# axiom_beta_plugin_module_3xPMOD_v1_1_1d7.net
KiCad netlist of a schematic drawn in EAGLE
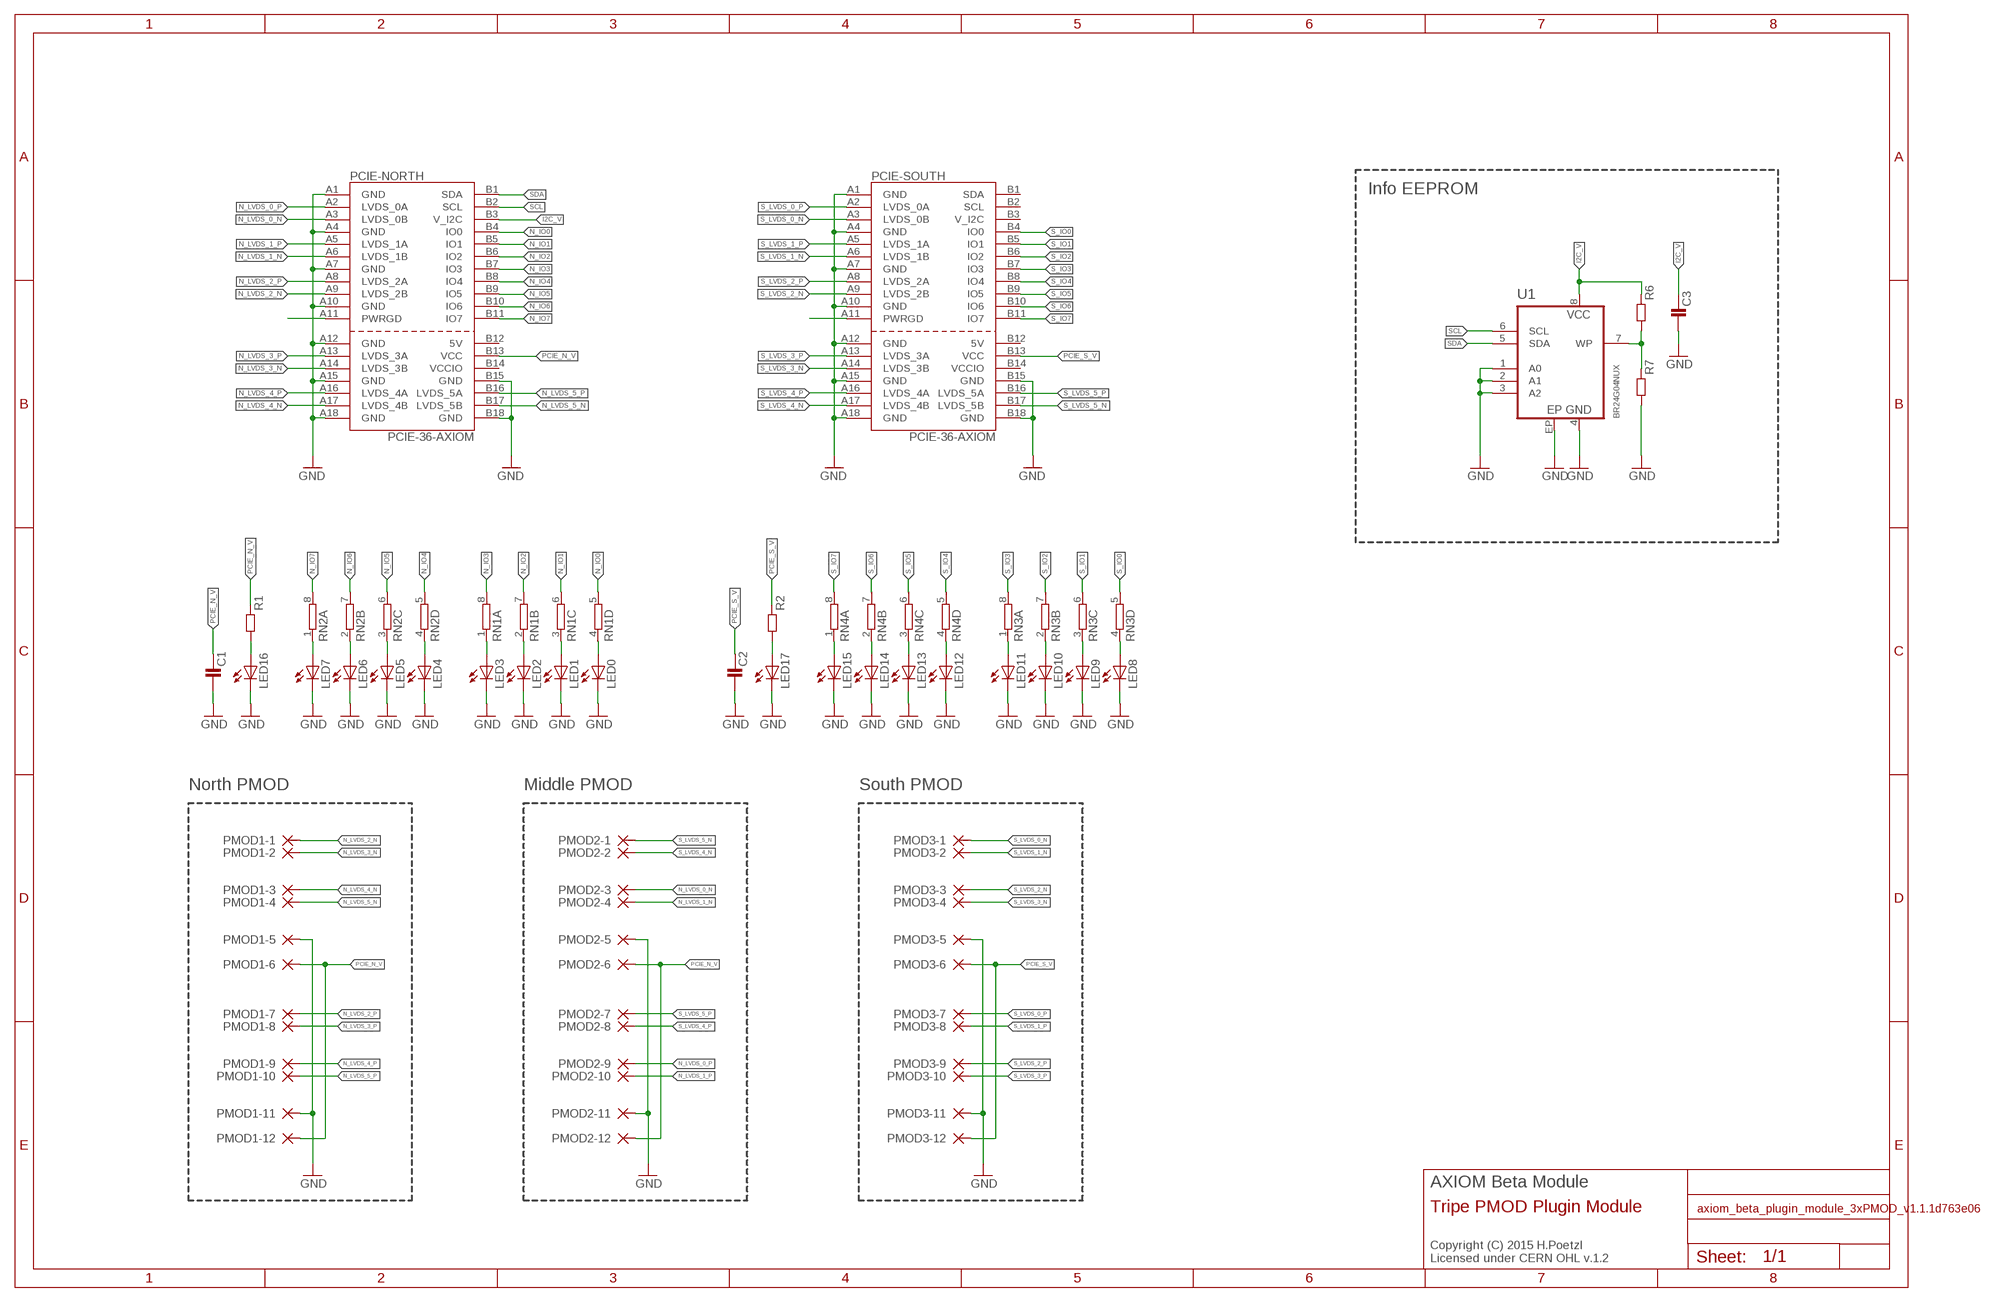
[diagram p0: schematic, sheet 1]

(export (version "E")
  (design (tool "Eeschema 10.0.6"))
  (components
    (comp (ref "C1")
      (value "C1206-A")
      (footprint "eagle-import:1206-A")
      (libsource (lib "eagle-import") (part "C1206-A"))
    )
    (comp (ref "C2")
      (value "C1206-A")
      (footprint "eagle-import:1206-A")
      (libsource (lib "eagle-import") (part "C1206-A"))
    )
    (comp (ref "C3")
      (value "C0402-B")
      (footprint "eagle-import:0402-B")
      (libsource (lib "eagle-import") (part "C0402-B"))
    )
    (comp (ref "LED0")
      (value "LEDCHIPLED_0603")
      (footprint "eagle-import:CHIPLED_0603")
      (libsource (lib "eagle-import") (part "LEDCHIPLED_0603"))
    )
    (comp (ref "LED1")
      (value "LEDCHIPLED_0603")
      (footprint "eagle-import:CHIPLED_0603")
      (libsource (lib "eagle-import") (part "LEDCHIPLED_0603"))
    )
    (comp (ref "LED2")
      (value "LEDCHIPLED_0603")
      (footprint "eagle-import:CHIPLED_0603")
      (libsource (lib "eagle-import") (part "LEDCHIPLED_0603"))
    )
    (comp (ref "LED3")
      (value "LEDCHIPLED_0603")
      (footprint "eagle-import:CHIPLED_0603")
      (libsource (lib "eagle-import") (part "LEDCHIPLED_0603"))
    )
    (comp (ref "LED4")
      (value "LEDCHIPLED_0603")
      (footprint "eagle-import:CHIPLED_0603")
      (libsource (lib "eagle-import") (part "LEDCHIPLED_0603"))
    )
    (comp (ref "LED5")
      (value "LEDCHIPLED_0603")
      (footprint "eagle-import:CHIPLED_0603")
      (libsource (lib "eagle-import") (part "LEDCHIPLED_0603"))
    )
    (comp (ref "LED6")
      (value "LEDCHIPLED_0603")
      (footprint "eagle-import:CHIPLED_0603")
      (libsource (lib "eagle-import") (part "LEDCHIPLED_0603"))
    )
    (comp (ref "LED7")
      (value "LEDCHIPLED_0603")
      (footprint "eagle-import:CHIPLED_0603")
      (libsource (lib "eagle-import") (part "LEDCHIPLED_0603"))
    )
    (comp (ref "LED8")
      (value "LEDCHIPLED_0603")
      (footprint "eagle-import:CHIPLED_0603")
      (libsource (lib "eagle-import") (part "LEDCHIPLED_0603"))
    )
    (comp (ref "LED9")
      (value "LEDCHIPLED_0603")
      (footprint "eagle-import:CHIPLED_0603")
      (libsource (lib "eagle-import") (part "LEDCHIPLED_0603"))
    )
    (comp (ref "LED10")
      (value "LEDCHIPLED_0603")
      (footprint "eagle-import:CHIPLED_0603")
      (libsource (lib "eagle-import") (part "LEDCHIPLED_0603"))
    )
    (comp (ref "LED11")
      (value "LEDCHIPLED_0603")
      (footprint "eagle-import:CHIPLED_0603")
      (libsource (lib "eagle-import") (part "LEDCHIPLED_0603"))
    )
    (comp (ref "LED12")
      (value "LEDCHIPLED_0603")
      (footprint "eagle-import:CHIPLED_0603")
      (libsource (lib "eagle-import") (part "LEDCHIPLED_0603"))
    )
    (comp (ref "LED13")
      (value "LEDCHIPLED_0603")
      (footprint "eagle-import:CHIPLED_0603")
      (libsource (lib "eagle-import") (part "LEDCHIPLED_0603"))
    )
    (comp (ref "LED14")
      (value "LEDCHIPLED_0603")
      (footprint "eagle-import:CHIPLED_0603")
      (libsource (lib "eagle-import") (part "LEDCHIPLED_0603"))
    )
    (comp (ref "LED15")
      (value "LEDCHIPLED_0603")
      (footprint "eagle-import:CHIPLED_0603")
      (libsource (lib "eagle-import") (part "LEDCHIPLED_0603"))
    )
    (comp (ref "LED16")
      (value "LEDCHIPLED_0603")
      (footprint "eagle-import:CHIPLED_0603")
      (libsource (lib "eagle-import") (part "LEDCHIPLED_0603"))
    )
    (comp (ref "LED17")
      (value "LEDCHIPLED_0603")
      (footprint "eagle-import:CHIPLED_0603")
      (libsource (lib "eagle-import") (part "LEDCHIPLED_0603"))
    )
    (comp (ref "PCIE-NORTH")
      (value "PCIE-36-AXIOM")
      (footprint "eagle-import:PCIE-36-AXIOM")
      (libsource (lib "eagle-import") (part "PCIE-36-AXIOM"))
    )
    (comp (ref "PCIE-SOUTH")
      (value "PCIE-36-AXIOM")
      (footprint "eagle-import:PCIE-36-AXIOM")
      (libsource (lib "eagle-import") (part "PCIE-36-AXIOM"))
    )
    (comp (ref "PMOD1-1")
      (value "SMD-PAD1.6X3.8MM-U")
      (footprint "eagle-import:1.6X3.8U-MM")
      (libsource (lib "eagle-import") (part "SMD-PAD1.6X3.8MM-U"))
    )
    (comp (ref "PMOD1-2")
      (value "SMD-PAD1.6X3.8MM-U")
      (footprint "eagle-import:1.6X3.8U-MM")
      (libsource (lib "eagle-import") (part "SMD-PAD1.6X3.8MM-U"))
    )
    (comp (ref "PMOD1-3")
      (value "SMD-PAD1.6X3.8MM-U")
      (footprint "eagle-import:1.6X3.8U-MM")
      (libsource (lib "eagle-import") (part "SMD-PAD1.6X3.8MM-U"))
    )
    (comp (ref "PMOD1-4")
      (value "SMD-PAD1.6X3.8MM-U")
      (footprint "eagle-import:1.6X3.8U-MM")
      (libsource (lib "eagle-import") (part "SMD-PAD1.6X3.8MM-U"))
    )
    (comp (ref "PMOD1-5")
      (value "SMD-PAD1.6X3.8MM-U")
      (footprint "eagle-import:1.6X3.8U-MM")
      (libsource (lib "eagle-import") (part "SMD-PAD1.6X3.8MM-U"))
    )
    (comp (ref "PMOD1-6")
      (value "SMD-PAD1.6X3.8MM-U")
      (footprint "eagle-import:1.6X3.8U-MM")
      (libsource (lib "eagle-import") (part "SMD-PAD1.6X3.8MM-U"))
    )
    (comp (ref "PMOD1-7")
      (value "SMD-PAD1.6X3.8MM-U")
      (footprint "eagle-import:1.6X3.8U-MM")
      (libsource (lib "eagle-import") (part "SMD-PAD1.6X3.8MM-U"))
    )
    (comp (ref "PMOD1-8")
      (value "SMD-PAD1.6X3.8MM-U")
      (footprint "eagle-import:1.6X3.8U-MM")
      (libsource (lib "eagle-import") (part "SMD-PAD1.6X3.8MM-U"))
    )
    (comp (ref "PMOD1-9")
      (value "SMD-PAD1.6X3.8MM-U")
      (footprint "eagle-import:1.6X3.8U-MM")
      (libsource (lib "eagle-import") (part "SMD-PAD1.6X3.8MM-U"))
    )
    (comp (ref "PMOD1-10")
      (value "SMD-PAD1.6X3.8MM-U")
      (footprint "eagle-import:1.6X3.8U-MM")
      (libsource (lib "eagle-import") (part "SMD-PAD1.6X3.8MM-U"))
    )
    (comp (ref "PMOD1-11")
      (value "SMD-PAD1.6X3.8MM-U")
      (footprint "eagle-import:1.6X3.8U-MM")
      (libsource (lib "eagle-import") (part "SMD-PAD1.6X3.8MM-U"))
    )
    (comp (ref "PMOD1-12")
      (value "SMD-PAD1.6X3.8MM-U")
      (footprint "eagle-import:1.6X3.8U-MM")
      (libsource (lib "eagle-import") (part "SMD-PAD1.6X3.8MM-U"))
    )
    (comp (ref "PMOD2-1")
      (value "SMD-PAD1.6X3.8MM-U")
      (footprint "eagle-import:1.6X3.8U-MM")
      (libsource (lib "eagle-import") (part "SMD-PAD1.6X3.8MM-U"))
    )
    (comp (ref "PMOD2-2")
      (value "SMD-PAD1.6X3.8MM-U")
      (footprint "eagle-import:1.6X3.8U-MM")
      (libsource (lib "eagle-import") (part "SMD-PAD1.6X3.8MM-U"))
    )
    (comp (ref "PMOD2-3")
      (value "SMD-PAD1.6X3.8MM-U")
      (footprint "eagle-import:1.6X3.8U-MM")
      (libsource (lib "eagle-import") (part "SMD-PAD1.6X3.8MM-U"))
    )
    (comp (ref "PMOD2-4")
      (value "SMD-PAD1.6X3.8MM-U")
      (footprint "eagle-import:1.6X3.8U-MM")
      (libsource (lib "eagle-import") (part "SMD-PAD1.6X3.8MM-U"))
    )
    (comp (ref "PMOD2-5")
      (value "SMD-PAD1.6X3.8MM-U")
      (footprint "eagle-import:1.6X3.8U-MM")
      (libsource (lib "eagle-import") (part "SMD-PAD1.6X3.8MM-U"))
    )
    (comp (ref "PMOD2-6")
      (value "SMD-PAD1.6X3.8MM-U")
      (footprint "eagle-import:1.6X3.8U-MM")
      (libsource (lib "eagle-import") (part "SMD-PAD1.6X3.8MM-U"))
    )
    (comp (ref "PMOD2-7")
      (value "SMD-PAD1.6X3.8MM-U")
      (footprint "eagle-import:1.6X3.8U-MM")
      (libsource (lib "eagle-import") (part "SMD-PAD1.6X3.8MM-U"))
    )
    (comp (ref "PMOD2-8")
      (value "SMD-PAD1.6X3.8MM-U")
      (footprint "eagle-import:1.6X3.8U-MM")
      (libsource (lib "eagle-import") (part "SMD-PAD1.6X3.8MM-U"))
    )
    (comp (ref "PMOD2-9")
      (value "SMD-PAD1.6X3.8MM-U")
      (footprint "eagle-import:1.6X3.8U-MM")
      (libsource (lib "eagle-import") (part "SMD-PAD1.6X3.8MM-U"))
    )
    (comp (ref "PMOD2-10")
      (value "SMD-PAD1.6X3.8MM-U")
      (footprint "eagle-import:1.6X3.8U-MM")
      (libsource (lib "eagle-import") (part "SMD-PAD1.6X3.8MM-U"))
    )
    (comp (ref "PMOD2-11")
      (value "SMD-PAD1.6X3.8MM-U")
      (footprint "eagle-import:1.6X3.8U-MM")
      (libsource (lib "eagle-import") (part "SMD-PAD1.6X3.8MM-U"))
    )
    (comp (ref "PMOD2-12")
      (value "SMD-PAD1.6X3.8MM-U")
      (footprint "eagle-import:1.6X3.8U-MM")
      (libsource (lib "eagle-import") (part "SMD-PAD1.6X3.8MM-U"))
    )
    (comp (ref "PMOD3-1")
      (value "SMD-PAD1.6X3.8MM-U")
      (footprint "eagle-import:1.6X3.8U-MM")
      (libsource (lib "eagle-import") (part "SMD-PAD1.6X3.8MM-U"))
    )
    (comp (ref "PMOD3-2")
      (value "SMD-PAD1.6X3.8MM-U")
      (footprint "eagle-import:1.6X3.8U-MM")
      (libsource (lib "eagle-import") (part "SMD-PAD1.6X3.8MM-U"))
    )
    (comp (ref "PMOD3-3")
      (value "SMD-PAD1.6X3.8MM-U")
      (footprint "eagle-import:1.6X3.8U-MM")
      (libsource (lib "eagle-import") (part "SMD-PAD1.6X3.8MM-U"))
    )
    (comp (ref "PMOD3-4")
      (value "SMD-PAD1.6X3.8MM-U")
      (footprint "eagle-import:1.6X3.8U-MM")
      (libsource (lib "eagle-import") (part "SMD-PAD1.6X3.8MM-U"))
    )
    (comp (ref "PMOD3-5")
      (value "SMD-PAD1.6X3.8MM-U")
      (footprint "eagle-import:1.6X3.8U-MM")
      (libsource (lib "eagle-import") (part "SMD-PAD1.6X3.8MM-U"))
    )
    (comp (ref "PMOD3-6")
      (value "SMD-PAD1.6X3.8MM-U")
      (footprint "eagle-import:1.6X3.8U-MM")
      (libsource (lib "eagle-import") (part "SMD-PAD1.6X3.8MM-U"))
    )
    (comp (ref "PMOD3-7")
      (value "SMD-PAD1.6X3.8MM-U")
      (footprint "eagle-import:1.6X3.8U-MM")
      (libsource (lib "eagle-import") (part "SMD-PAD1.6X3.8MM-U"))
    )
    (comp (ref "PMOD3-8")
      (value "SMD-PAD1.6X3.8MM-U")
      (footprint "eagle-import:1.6X3.8U-MM")
      (libsource (lib "eagle-import") (part "SMD-PAD1.6X3.8MM-U"))
    )
    (comp (ref "PMOD3-9")
      (value "SMD-PAD1.6X3.8MM-U")
      (footprint "eagle-import:1.6X3.8U-MM")
      (libsource (lib "eagle-import") (part "SMD-PAD1.6X3.8MM-U"))
    )
    (comp (ref "PMOD3-10")
      (value "SMD-PAD1.6X3.8MM-U")
      (footprint "eagle-import:1.6X3.8U-MM")
      (libsource (lib "eagle-import") (part "SMD-PAD1.6X3.8MM-U"))
    )
    (comp (ref "PMOD3-11")
      (value "SMD-PAD1.6X3.8MM-U")
      (footprint "eagle-import:1.6X3.8U-MM")
      (libsource (lib "eagle-import") (part "SMD-PAD1.6X3.8MM-U"))
    )
    (comp (ref "PMOD3-12")
      (value "SMD-PAD1.6X3.8MM-U")
      (footprint "eagle-import:1.6X3.8U-MM")
      (libsource (lib "eagle-import") (part "SMD-PAD1.6X3.8MM-U"))
    )
    (comp (ref "R1")
      (value "R0402-B")
      (footprint "eagle-import:0402-B")
      (libsource (lib "eagle-import") (part "R0402-B"))
    )
    (comp (ref "R2")
      (value "R0402-B")
      (footprint "eagle-import:0402-B")
      (libsource (lib "eagle-import") (part "R0402-B"))
    )
    (comp (ref "R6")
      (value "R0402-B")
      (footprint "eagle-import:0402-B")
      (libsource (lib "eagle-import") (part "R0402-B"))
    )
    (comp (ref "R7")
      (value "R0402-B")
      (footprint "eagle-import:0402-B")
      (libsource (lib "eagle-import") (part "R0402-B"))
    )
    (comp (ref "RN1")
      (value "4R-NCAY16")
      (footprint "eagle-import:CAY16")
      (libsource (lib "eagle-import") (part "4R-NCAY16"))
    )
    (comp (ref "RN2")
      (value "4R-NCAY16")
      (footprint "eagle-import:CAY16")
      (libsource (lib "eagle-import") (part "4R-NCAY16"))
    )
    (comp (ref "RN3")
      (value "4R-NCAY16")
      (footprint "eagle-import:CAY16")
      (libsource (lib "eagle-import") (part "4R-NCAY16"))
    )
    (comp (ref "RN4")
      (value "4R-NCAY16")
      (footprint "eagle-import:CAY16")
      (libsource (lib "eagle-import") (part "4R-NCAY16"))
    )
    (comp (ref "U1")
      (value "BR24G04NUX")
      (footprint "eagle-import:DFN200X300X100-9N")
      (libsource (lib "eagle-import") (part "BR24G04NUX"))
    )
  )
  (nets
    (net (code "1") (name "GND") (class "Default")
      (node (ref "C1") (pin "2") (pinfunction "2_2") (pintype "passive"))
      (node (ref "C2") (pin "2") (pinfunction "2_2") (pintype "passive"))
      (node (ref "C3") (pin "2") (pinfunction "2_2") (pintype "passive"))
      (node (ref "LED0") (pin "C") (pinfunction "C_C") (pintype "passive"))
      (node (ref "LED1") (pin "C") (pinfunction "C_C") (pintype "passive"))
      (node (ref "LED10") (pin "C") (pinfunction "C_C") (pintype "passive"))
      (node (ref "LED11") (pin "C") (pinfunction "C_C") (pintype "passive"))
      (node (ref "LED12") (pin "C") (pinfunction "C_C") (pintype "passive"))
      (node (ref "LED13") (pin "C") (pinfunction "C_C") (pintype "passive"))
      (node (ref "LED14") (pin "C") (pinfunction "C_C") (pintype "passive"))
      (node (ref "LED15") (pin "C") (pinfunction "C_C") (pintype "passive"))
      (node (ref "LED16") (pin "C") (pinfunction "C_C") (pintype "passive"))
      (node (ref "LED17") (pin "C") (pinfunction "C_C") (pintype "passive"))
      (node (ref "LED2") (pin "C") (pinfunction "C_C") (pintype "passive"))
      (node (ref "LED3") (pin "C") (pinfunction "C_C") (pintype "passive"))
      (node (ref "LED4") (pin "C") (pinfunction "C_C") (pintype "passive"))
      (node (ref "LED5") (pin "C") (pinfunction "C_C") (pintype "passive"))
      (node (ref "LED6") (pin "C") (pinfunction "C_C") (pintype "passive"))
      (node (ref "LED7") (pin "C") (pinfunction "C_C") (pintype "passive"))
      (node (ref "LED8") (pin "C") (pinfunction "C_C") (pintype "passive"))
      (node (ref "LED9") (pin "C") (pinfunction "C_C") (pintype "passive"))
      (node (ref "PCIE-NORTH") (pin "A1") (pinfunction "GND_A1") (pintype "passive"))
      (node (ref "PCIE-NORTH") (pin "A10") (pinfunction "GND_A10") (pintype "passive"))
      (node (ref "PCIE-NORTH") (pin "A12") (pinfunction "GND_A12") (pintype "passive"))
      (node (ref "PCIE-NORTH") (pin "A15") (pinfunction "GND_A15") (pintype "passive"))
      (node (ref "PCIE-NORTH") (pin "A18") (pinfunction "GND_A18") (pintype "passive"))
      (node (ref "PCIE-NORTH") (pin "A4") (pinfunction "GND_A4") (pintype "passive"))
      (node (ref "PCIE-NORTH") (pin "A7") (pinfunction "GND_A7") (pintype "passive"))
      (node (ref "PCIE-NORTH") (pin "B15") (pinfunction "GND_B15") (pintype "passive"))
      (node (ref "PCIE-NORTH") (pin "B18") (pinfunction "GND_B18") (pintype "passive"))
      (node (ref "PCIE-SOUTH") (pin "A1") (pinfunction "GND_A1") (pintype "passive"))
      (node (ref "PCIE-SOUTH") (pin "A10") (pinfunction "GND_A10") (pintype "passive"))
      (node (ref "PCIE-SOUTH") (pin "A12") (pinfunction "GND_A12") (pintype "passive"))
      (node (ref "PCIE-SOUTH") (pin "A15") (pinfunction "GND_A15") (pintype "passive"))
      (node (ref "PCIE-SOUTH") (pin "A18") (pinfunction "GND_A18") (pintype "passive"))
      (node (ref "PCIE-SOUTH") (pin "A4") (pinfunction "GND_A4") (pintype "passive"))
      (node (ref "PCIE-SOUTH") (pin "A7") (pinfunction "GND_A7") (pintype "passive"))
      (node (ref "PCIE-SOUTH") (pin "B15") (pinfunction "GND_B15") (pintype "passive"))
      (node (ref "PCIE-SOUTH") (pin "B18") (pinfunction "GND_B18") (pintype "passive"))
      (node (ref "PMOD1-11") (pin "1") (pinfunction "P_1") (pintype "passive"))
      (node (ref "PMOD1-5") (pin "1") (pinfunction "P_1") (pintype "passive"))
      (node (ref "PMOD2-11") (pin "1") (pinfunction "P_1") (pintype "passive"))
      (node (ref "PMOD2-5") (pin "1") (pinfunction "P_1") (pintype "passive"))
      (node (ref "PMOD3-11") (pin "1") (pinfunction "P_1") (pintype "passive"))
      (node (ref "PMOD3-5") (pin "1") (pinfunction "P_1") (pintype "passive"))
      (node (ref "R7") (pin "2") (pinfunction "2_2") (pintype "passive"))
      (node (ref "U1") (pin "1") (pinfunction "A0_1") (pintype "input"))
      (node (ref "U1") (pin "2") (pinfunction "A1_2") (pintype "input"))
      (node (ref "U1") (pin "3") (pinfunction "A2_3") (pintype "input"))
      (node (ref "U1") (pin "4") (pinfunction "GND_4") (pintype "passive"))
      (node (ref "U1") (pin "EP") (pinfunction "EP_EP") (pintype "passive"))
    )
    (net (code "2") (name "I2C_V") (class "Default")
      (node (ref "C3") (pin "1") (pinfunction "1_1") (pintype "passive"))
      (node (ref "PCIE-NORTH") (pin "B3") (pinfunction "V_I2C_B3") (pintype "passive"))
      (node (ref "R6") (pin "1") (pinfunction "1_1") (pintype "passive"))
      (node (ref "U1") (pin "8") (pinfunction "VCC_8") (pintype "power_in"))
    )
    (net (code "3") (name "N_IO0") (class "Default")
      (node (ref "PCIE-NORTH") (pin "B4") (pinfunction "IO0_B4") (pintype "passive"))
      (node (ref "RN1") (pin "5") (pinfunction "2_5") (pintype "passive"))
    )
    (net (code "4") (name "N_IO1") (class "Default")
      (node (ref "PCIE-NORTH") (pin "B5") (pinfunction "IO1_B5") (pintype "passive"))
      (node (ref "RN1") (pin "6") (pinfunction "2_6") (pintype "passive"))
    )
    (net (code "5") (name "N_IO2") (class "Default")
      (node (ref "PCIE-NORTH") (pin "B6") (pinfunction "IO2_B6") (pintype "passive"))
      (node (ref "RN1") (pin "7") (pinfunction "2_7") (pintype "passive"))
    )
    (net (code "6") (name "N_IO3") (class "Default")
      (node (ref "PCIE-NORTH") (pin "B7") (pinfunction "IO3_B7") (pintype "passive"))
      (node (ref "RN1") (pin "8") (pinfunction "2_8") (pintype "passive"))
    )
    (net (code "7") (name "N_IO4") (class "Default")
      (node (ref "PCIE-NORTH") (pin "B8") (pinfunction "IO4_B8") (pintype "passive"))
      (node (ref "RN2") (pin "5") (pinfunction "2_5") (pintype "passive"))
    )
    (net (code "8") (name "N_IO5") (class "Default")
      (node (ref "PCIE-NORTH") (pin "B9") (pinfunction "IO5_B9") (pintype "passive"))
      (node (ref "RN2") (pin "6") (pinfunction "2_6") (pintype "passive"))
    )
    (net (code "9") (name "N_IO6") (class "Default")
      (node (ref "PCIE-NORTH") (pin "B10") (pinfunction "IO6_B10") (pintype "passive"))
      (node (ref "RN2") (pin "7") (pinfunction "2_7") (pintype "passive"))
    )
    (net (code "10") (name "N_IO7") (class "Default")
      (node (ref "PCIE-NORTH") (pin "B11") (pinfunction "IO7_B11") (pintype "passive"))
      (node (ref "RN2") (pin "8") (pinfunction "2_8") (pintype "passive"))
    )
    (net (code "11") (name "N_LVDS_0_N") (class "Default")
      (node (ref "PCIE-NORTH") (pin "A3") (pinfunction "LVDS_0B_A3") (pintype "passive"))
      (node (ref "PMOD2-3") (pin "1") (pinfunction "P_1") (pintype "passive"))
    )
    (net (code "12") (name "N_LVDS_0_P") (class "Default")
      (node (ref "PCIE-NORTH") (pin "A2") (pinfunction "LVDS_0A_A2") (pintype "passive"))
      (node (ref "PMOD2-9") (pin "1") (pinfunction "P_1") (pintype "passive"))
    )
    (net (code "13") (name "N_LVDS_1_N") (class "Default")
      (node (ref "PCIE-NORTH") (pin "A6") (pinfunction "LVDS_1B_A6") (pintype "passive"))
      (node (ref "PMOD2-4") (pin "1") (pinfunction "P_1") (pintype "passive"))
    )
    (net (code "14") (name "N_LVDS_1_P") (class "Default")
      (node (ref "PCIE-NORTH") (pin "A5") (pinfunction "LVDS_1A_A5") (pintype "passive"))
      (node (ref "PMOD2-10") (pin "1") (pinfunction "P_1") (pintype "passive"))
    )
    (net (code "15") (name "N_LVDS_2_N") (class "Default")
      (node (ref "PCIE-NORTH") (pin "A9") (pinfunction "LVDS_2B_A9") (pintype "passive"))
      (node (ref "PMOD1-1") (pin "1") (pinfunction "P_1") (pintype "passive"))
    )
    (net (code "16") (name "N_LVDS_2_P") (class "Default")
      (node (ref "PCIE-NORTH") (pin "A8") (pinfunction "LVDS_2A_A8") (pintype "passive"))
      (node (ref "PMOD1-7") (pin "1") (pinfunction "P_1") (pintype "passive"))
    )
    (net (code "17") (name "N_LVDS_3_N") (class "Default")
      (node (ref "PCIE-NORTH") (pin "A14") (pinfunction "LVDS_3B_A14") (pintype "passive"))
      (node (ref "PMOD1-2") (pin "1") (pinfunction "P_1") (pintype "passive"))
    )
    (net (code "18") (name "N_LVDS_3_P") (class "Default")
      (node (ref "PCIE-NORTH") (pin "A13") (pinfunction "LVDS_3A_A13") (pintype "passive"))
      (node (ref "PMOD1-8") (pin "1") (pinfunction "P_1") (pintype "passive"))
    )
    (net (code "19") (name "N_LVDS_4_N") (class "Default")
      (node (ref "PCIE-NORTH") (pin "A17") (pinfunction "LVDS_4B_A17") (pintype "passive"))
      (node (ref "PMOD1-3") (pin "1") (pinfunction "P_1") (pintype "passive"))
    )
    (net (code "20") (name "N_LVDS_4_P") (class "Default")
      (node (ref "PCIE-NORTH") (pin "A16") (pinfunction "LVDS_4A_A16") (pintype "passive"))
      (node (ref "PMOD1-9") (pin "1") (pinfunction "P_1") (pintype "passive"))
    )
    (net (code "21") (name "N_LVDS_5_N") (class "Default")
      (node (ref "PCIE-NORTH") (pin "B17") (pinfunction "LVDS_5B_B17") (pintype "passive"))
      (node (ref "PMOD1-4") (pin "1") (pinfunction "P_1") (pintype "passive"))
    )
    (net (code "22") (name "N_LVDS_5_P") (class "Default")
      (node (ref "PCIE-NORTH") (pin "B16") (pinfunction "LVDS_5A_B16") (pintype "passive"))
      (node (ref "PMOD1-10") (pin "1") (pinfunction "P_1") (pintype "passive"))
    )
    (net (code "23") (name "Net-(LED3-PadA)") (class "Default")
      (node (ref "LED3") (pin "A") (pinfunction "A_A") (pintype "passive"))
      (node (ref "RN1") (pin "1") (pinfunction "1_1") (pintype "passive"))
    )
    (net (code "24") (name "Net-(LED7-PadA)") (class "Default")
      (node (ref "LED7") (pin "A") (pinfunction "A_A") (pintype "passive"))
      (node (ref "RN2") (pin "1") (pinfunction "1_1") (pintype "passive"))
    )
    (net (code "25") (name "Net-(LED11-PadA)") (class "Default")
      (node (ref "LED11") (pin "A") (pinfunction "A_A") (pintype "passive"))
      (node (ref "RN3") (pin "1") (pinfunction "1_1") (pintype "passive"))
    )
    (net (code "26") (name "Net-(LED15-PadA)") (class "Default")
      (node (ref "LED15") (pin "A") (pinfunction "A_A") (pintype "passive"))
      (node (ref "RN4") (pin "1") (pinfunction "1_1") (pintype "passive"))
    )
    (net (code "27") (name "Net-(LED16-PadA)") (class "Default")
      (node (ref "LED16") (pin "A") (pinfunction "A_A") (pintype "passive"))
      (node (ref "R1") (pin "2") (pinfunction "2_2") (pintype "passive"))
    )
    (net (code "28") (name "Net-(LED17-PadA)") (class "Default")
      (node (ref "LED17") (pin "A") (pinfunction "A_A") (pintype "passive"))
      (node (ref "R2") (pin "2") (pinfunction "2_2") (pintype "passive"))
    )
    (net (code "29") (name "Net-(RN1B-1)") (class "Default")
      (node (ref "LED2") (pin "A") (pinfunction "A_A") (pintype "passive"))
      (node (ref "RN1") (pin "2") (pinfunction "1_2") (pintype "passive"))
    )
    (net (code "30") (name "Net-(RN1C-1)") (class "Default")
      (node (ref "LED1") (pin "A") (pinfunction "A_A") (pintype "passive"))
      (node (ref "RN1") (pin "3") (pinfunction "1_3") (pintype "passive"))
    )
    (net (code "31") (name "Net-(RN1D-1)") (class "Default")
      (node (ref "LED0") (pin "A") (pinfunction "A_A") (pintype "passive"))
      (node (ref "RN1") (pin "4") (pinfunction "1_4") (pintype "passive"))
    )
    (net (code "32") (name "Net-(RN2B-1)") (class "Default")
      (node (ref "LED6") (pin "A") (pinfunction "A_A") (pintype "passive"))
      (node (ref "RN2") (pin "2") (pinfunction "1_2") (pintype "passive"))
    )
    (net (code "33") (name "Net-(RN2C-1)") (class "Default")
      (node (ref "LED5") (pin "A") (pinfunction "A_A") (pintype "passive"))
      (node (ref "RN2") (pin "3") (pinfunction "1_3") (pintype "passive"))
    )
    (net (code "34") (name "Net-(RN2D-1)") (class "Default")
      (node (ref "LED4") (pin "A") (pinfunction "A_A") (pintype "passive"))
      (node (ref "RN2") (pin "4") (pinfunction "1_4") (pintype "passive"))
    )
    (net (code "35") (name "Net-(RN3B-1)") (class "Default")
      (node (ref "LED10") (pin "A") (pinfunction "A_A") (pintype "passive"))
      (node (ref "RN3") (pin "2") (pinfunction "1_2") (pintype "passive"))
    )
    (net (code "36") (name "Net-(RN3C-1)") (class "Default")
      (node (ref "LED9") (pin "A") (pinfunction "A_A") (pintype "passive"))
      (node (ref "RN3") (pin "3") (pinfunction "1_3") (pintype "passive"))
    )
    (net (code "37") (name "Net-(RN3D-1)") (class "Default")
      (node (ref "LED8") (pin "A") (pinfunction "A_A") (pintype "passive"))
      (node (ref "RN3") (pin "4") (pinfunction "1_4") (pintype "passive"))
    )
    (net (code "38") (name "Net-(RN4B-1)") (class "Default")
      (node (ref "LED14") (pin "A") (pinfunction "A_A") (pintype "passive"))
      (node (ref "RN4") (pin "2") (pinfunction "1_2") (pintype "passive"))
    )
    (net (code "39") (name "Net-(RN4C-1)") (class "Default")
      (node (ref "LED13") (pin "A") (pinfunction "A_A") (pintype "passive"))
      (node (ref "RN4") (pin "3") (pinfunction "1_3") (pintype "passive"))
    )
    (net (code "40") (name "Net-(RN4D-1)") (class "Default")
      (node (ref "LED12") (pin "A") (pinfunction "A_A") (pintype "passive"))
      (node (ref "RN4") (pin "4") (pinfunction "1_4") (pintype "passive"))
    )
    (net (code "41") (name "Net-(U1-WP)") (class "Default")
      (node (ref "R6") (pin "2") (pinfunction "2_2") (pintype "passive"))
      (node (ref "R7") (pin "1") (pinfunction "1_1") (pintype "passive"))
      (node (ref "U1") (pin "7") (pinfunction "WP_7") (pintype "input"))
    )
    (net (code "42") (name "PCIE_N_V") (class "Default")
      (node (ref "C1") (pin "1") (pinfunction "1_1") (pintype "passive"))
      (node (ref "PCIE-NORTH") (pin "B13") (pinfunction "VCC_B13") (pintype "passive"))
      (node (ref "PMOD1-12") (pin "1") (pinfunction "P_1") (pintype "passive"))
      (node (ref "PMOD1-6") (pin "1") (pinfunction "P_1") (pintype "passive"))
      (node (ref "PMOD2-12") (pin "1") (pinfunction "P_1") (pintype "passive"))
      (node (ref "PMOD2-6") (pin "1") (pinfunction "P_1") (pintype "passive"))
      (node (ref "R1") (pin "1") (pinfunction "1_1") (pintype "passive"))
    )
    (net (code "43") (name "PCIE_S_V") (class "Default")
      (node (ref "C2") (pin "1") (pinfunction "1_1") (pintype "passive"))
      (node (ref "PCIE-SOUTH") (pin "B13") (pinfunction "VCC_B13") (pintype "passive"))
      (node (ref "PMOD3-12") (pin "1") (pinfunction "P_1") (pintype "passive"))
      (node (ref "PMOD3-6") (pin "1") (pinfunction "P_1") (pintype "passive"))
      (node (ref "R2") (pin "1") (pinfunction "1_1") (pintype "passive"))
    )
    (net (code "44") (name "SCL") (class "Default")
      (node (ref "PCIE-NORTH") (pin "B2") (pinfunction "SCL_B2") (pintype "passive"))
      (node (ref "U1") (pin "6") (pinfunction "SCL_6") (pintype "input"))
    )
    (net (code "45") (name "SDA") (class "Default")
      (node (ref "PCIE-NORTH") (pin "B1") (pinfunction "SDA_B1") (pintype "passive"))
      (node (ref "U1") (pin "5") (pinfunction "SDA_5") (pintype "bidirectional"))
    )
    (net (code "46") (name "S_IO0") (class "Default")
      (node (ref "PCIE-SOUTH") (pin "B4") (pinfunction "IO0_B4") (pintype "passive"))
      (node (ref "RN3") (pin "5") (pinfunction "2_5") (pintype "passive"))
    )
    (net (code "47") (name "S_IO1") (class "Default")
      (node (ref "PCIE-SOUTH") (pin "B5") (pinfunction "IO1_B5") (pintype "passive"))
      (node (ref "RN3") (pin "6") (pinfunction "2_6") (pintype "passive"))
    )
    (net (code "48") (name "S_IO2") (class "Default")
      (node (ref "PCIE-SOUTH") (pin "B6") (pinfunction "IO2_B6") (pintype "passive"))
      (node (ref "RN3") (pin "7") (pinfunction "2_7") (pintype "passive"))
    )
    (net (code "49") (name "S_IO3") (class "Default")
      (node (ref "PCIE-SOUTH") (pin "B7") (pinfunction "IO3_B7") (pintype "passive"))
      (node (ref "RN3") (pin "8") (pinfunction "2_8") (pintype "passive"))
    )
    (net (code "50") (name "S_IO4") (class "Default")
      (node (ref "PCIE-SOUTH") (pin "B8") (pinfunction "IO4_B8") (pintype "passive"))
      (node (ref "RN4") (pin "5") (pinfunction "2_5") (pintype "passive"))
    )
    (net (code "51") (name "S_IO5") (class "Default")
      (node (ref "PCIE-SOUTH") (pin "B9") (pinfunction "IO5_B9") (pintype "passive"))
      (node (ref "RN4") (pin "6") (pinfunction "2_6") (pintype "passive"))
    )
    (net (code "52") (name "S_IO6") (class "Default")
      (node (ref "PCIE-SOUTH") (pin "B10") (pinfunction "IO6_B10") (pintype "passive"))
      (node (ref "RN4") (pin "7") (pinfunction "2_7") (pintype "passive"))
    )
    (net (code "53") (name "S_IO7") (class "Default")
      (node (ref "PCIE-SOUTH") (pin "B11") (pinfunction "IO7_B11") (pintype "passive"))
      (node (ref "RN4") (pin "8") (pinfunction "2_8") (pintype "passive"))
    )
    (net (code "54") (name "S_LVDS_0_N") (class "Default")
      (node (ref "PCIE-SOUTH") (pin "A3") (pinfunction "LVDS_0B_A3") (pintype "passive"))
      (node (ref "PMOD3-1") (pin "1") (pinfunction "P_1") (pintype "passive"))
    )
    (net (code "55") (name "S_LVDS_0_P") (class "Default")
      (node (ref "PCIE-SOUTH") (pin "A2") (pinfunction "LVDS_0A_A2") (pintype "passive"))
      (node (ref "PMOD3-7") (pin "1") (pinfunction "P_1") (pintype "passive"))
    )
    (net (code "56") (name "S_LVDS_1_N") (class "Default")
      (node (ref "PCIE-SOUTH") (pin "A6") (pinfunction "LVDS_1B_A6") (pintype "passive"))
      (node (ref "PMOD3-2") (pin "1") (pinfunction "P_1") (pintype "passive"))
    )
    (net (code "57") (name "S_LVDS_1_P") (class "Default")
      (node (ref "PCIE-SOUTH") (pin "A5") (pinfunction "LVDS_1A_A5") (pintype "passive"))
      (node (ref "PMOD3-8") (pin "1") (pinfunction "P_1") (pintype "passive"))
    )
    (net (code "58") (name "S_LVDS_2_N") (class "Default")
      (node (ref "PCIE-SOUTH") (pin "A9") (pinfunction "LVDS_2B_A9") (pintype "passive"))
      (node (ref "PMOD3-3") (pin "1") (pinfunction "P_1") (pintype "passive"))
    )
    (net (code "59") (name "S_LVDS_2_P") (class "Default")
      (node (ref "PCIE-SOUTH") (pin "A8") (pinfunction "LVDS_2A_A8") (pintype "passive"))
      (node (ref "PMOD3-9") (pin "1") (pinfunction "P_1") (pintype "passive"))
    )
    (net (code "60") (name "S_LVDS_3_N") (class "Default")
      (node (ref "PCIE-SOUTH") (pin "A14") (pinfunction "LVDS_3B_A14") (pintype "passive"))
      (node (ref "PMOD3-4") (pin "1") (pinfunction "P_1") (pintype "passive"))
    )
    (net (code "61") (name "S_LVDS_3_P") (class "Default")
      (node (ref "PCIE-SOUTH") (pin "A13") (pinfunction "LVDS_3A_A13") (pintype "passive"))
      (node (ref "PMOD3-10") (pin "1") (pinfunction "P_1") (pintype "passive"))
    )
    (net (code "62") (name "S_LVDS_4_N") (class "Default")
      (node (ref "PCIE-SOUTH") (pin "A17") (pinfunction "LVDS_4B_A17") (pintype "passive"))
      (node (ref "PMOD2-2") (pin "1") (pinfunction "P_1") (pintype "passive"))
    )
    (net (code "63") (name "S_LVDS_4_P") (class "Default")
      (node (ref "PCIE-SOUTH") (pin "A16") (pinfunction "LVDS_4A_A16") (pintype "passive"))
      (node (ref "PMOD2-8") (pin "1") (pinfunction "P_1") (pintype "passive"))
    )
    (net (code "64") (name "S_LVDS_5_N") (class "Default")
      (node (ref "PCIE-SOUTH") (pin "B17") (pinfunction "LVDS_5B_B17") (pintype "passive"))
      (node (ref "PMOD2-1") (pin "1") (pinfunction "P_1") (pintype "passive"))
    )
    (net (code "65") (name "S_LVDS_5_P") (class "Default")
      (node (ref "PCIE-SOUTH") (pin "B16") (pinfunction "LVDS_5A_B16") (pintype "passive"))
      (node (ref "PMOD2-7") (pin "1") (pinfunction "P_1") (pintype "passive"))
    )
    (net (code "66") (name "unconnected-(PCIE-NORTH-5V-PadB12)") (class "Default")
      (node (ref "PCIE-NORTH") (pin "B12") (pinfunction "5V_B12") (pintype "passive"))
    )
    (net (code "67") (name "unconnected-(PCIE-NORTH-PWRGD-PadA11)") (class "Default")
      (node (ref "PCIE-NORTH") (pin "A11") (pinfunction "PWRGD_A11") (pintype "passive"))
    )
    (net (code "68") (name "unconnected-(PCIE-NORTH-VCCIO-PadB14)") (class "Default")
      (node (ref "PCIE-NORTH") (pin "B14") (pinfunction "VCCIO_B14") (pintype "passive"))
    )
    (net (code "69") (name "unconnected-(PCIE-SOUTH-5V-PadB12)") (class "Default")
      (node (ref "PCIE-SOUTH") (pin "B12") (pinfunction "5V_B12") (pintype "passive"))
    )
    (net (code "70") (name "unconnected-(PCIE-SOUTH-PWRGD-PadA11)") (class "Default")
      (node (ref "PCIE-SOUTH") (pin "A11") (pinfunction "PWRGD_A11") (pintype "passive"))
    )
    (net (code "71") (name "unconnected-(PCIE-SOUTH-SCL-PadB2)") (class "Default")
      (node (ref "PCIE-SOUTH") (pin "B2") (pinfunction "SCL_B2") (pintype "passive"))
    )
    (net (code "72") (name "unconnected-(PCIE-SOUTH-SDA-PadB1)") (class "Default")
      (node (ref "PCIE-SOUTH") (pin "B1") (pinfunction "SDA_B1") (pintype "passive"))
    )
    (net (code "73") (name "unconnected-(PCIE-SOUTH-VCCIO-PadB14)") (class "Default")
      (node (ref "PCIE-SOUTH") (pin "B14") (pinfunction "VCCIO_B14") (pintype "passive"))
    )
    (net (code "74") (name "unconnected-(PCIE-SOUTH-V_I2C-PadB3)") (class "Default")
      (node (ref "PCIE-SOUTH") (pin "B3") (pinfunction "V_I2C_B3") (pintype "passive"))
    )
  )
)
